# POWER_IO.net
KiCad netlist of a schematic drawn in Altium Designer
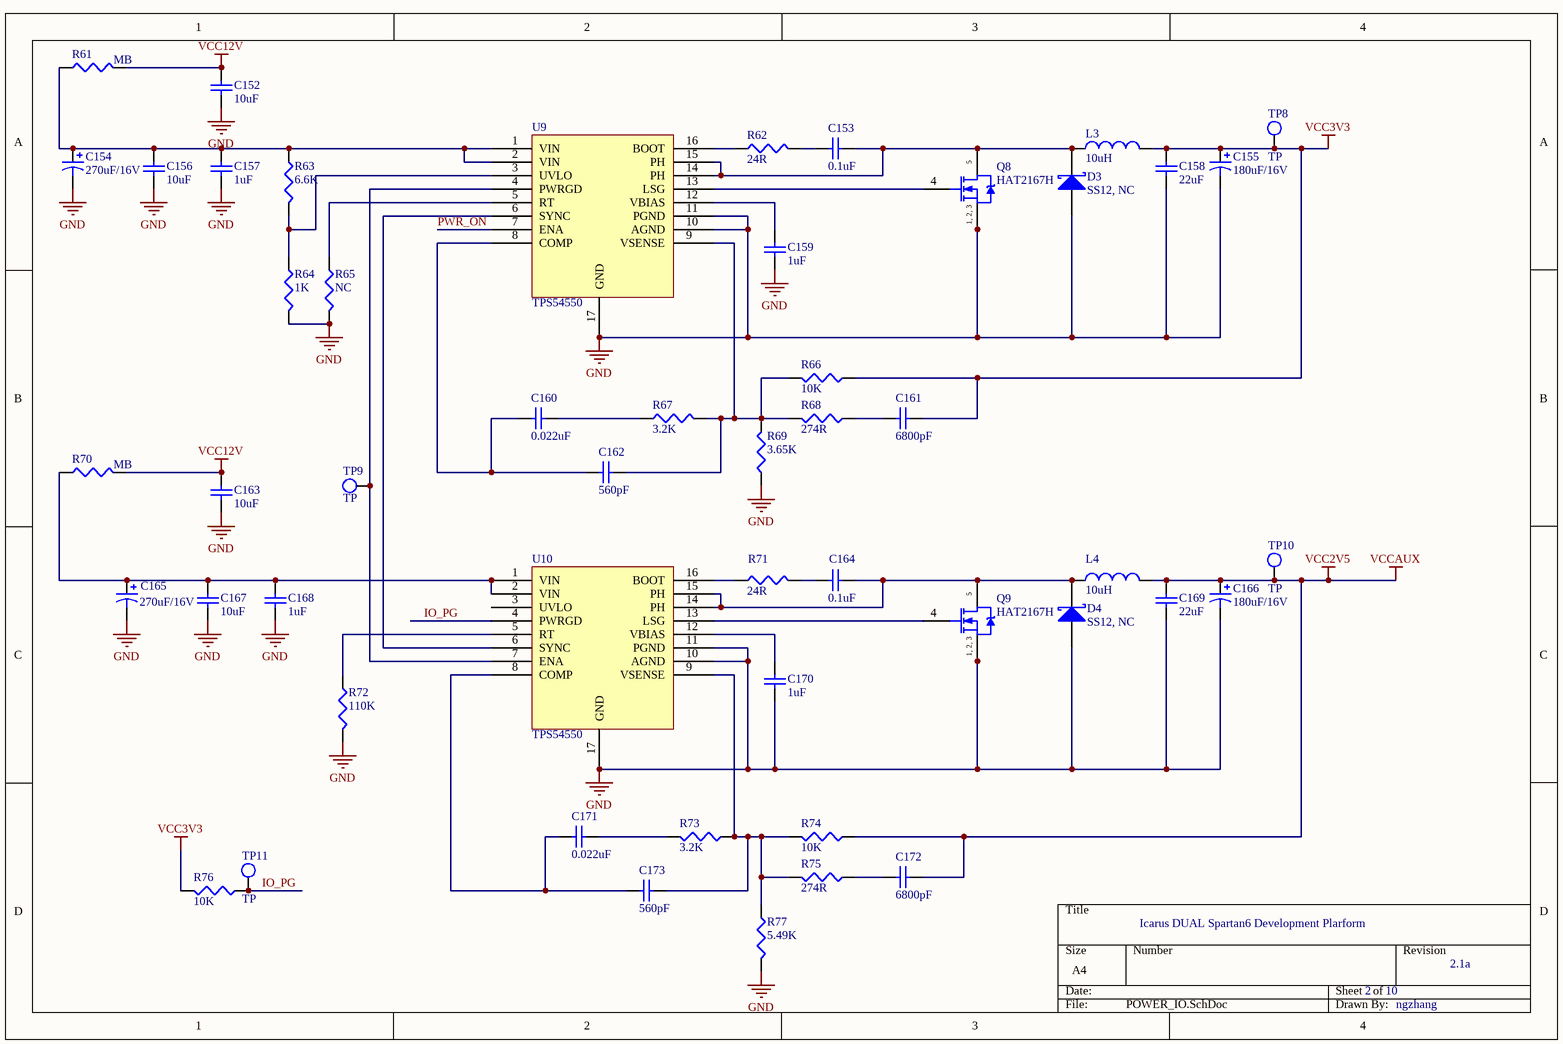
[diagram p0: POWER_IO.SchDoc]

(export (version "E")
  (design (tool "Eeschema 10.0.6"))
  (components
    (comp (ref "C152")
      (value "10uF")
      (footprint "C1206")
      (description "Capacitor (Semiconductor SIM Model)")
      (fields (field (name "PUBLISHER") "Altium Limited"))
      (libsource (lib "Miscellaneous Devices") (part "Cap Semi"))
    )
    (comp (ref "C153")
      (value "0.1uF")
      (footprint "1608[0603]")
      (description "Capacitor (Semiconductor SIM Model)")
      (fields (field (name "PUBLISHER") "Altium Limited"))
      (libsource (lib "Miscellaneous Devices") (part "Cap Semi"))
    )
    (comp (ref "C154")
      (value "270uF/16V")
      (footprint "CAP8X8")
      (description "Polarized Capacitor (Surface Mount)")
      (fields (field (name "PUBLISHER") "Altium Limited"))
      (libsource (lib "Miscellaneous Devices") (part "Cap Pol3"))
    )
    (comp (ref "C155")
      (value "180uF/16V")
      (footprint "CAP8X8")
      (description "Polarized Capacitor (Surface Mount)")
      (fields (field (name "PUBLISHER") "Altium Limited"))
      (libsource (lib "Miscellaneous Devices") (part "Cap Pol3"))
    )
    (comp (ref "C156")
      (value "10uF")
      (footprint "C1206")
      (description "Capacitor (Semiconductor SIM Model)")
      (fields (field (name "PUBLISHER") "Altium Limited"))
      (libsource (lib "Miscellaneous Devices") (part "Cap Semi"))
    )
    (comp (ref "C157")
      (value "1uF")
      (footprint "1608[0603]")
      (description "Capacitor (Semiconductor SIM Model)")
      (fields (field (name "PUBLISHER") "Altium Limited"))
      (libsource (lib "Miscellaneous Devices") (part "Cap Semi"))
    )
    (comp (ref "C158")
      (value "22uF")
      (footprint "C1206")
      (description "Capacitor (Semiconductor SIM Model)")
      (fields (field (name "PUBLISHER") "Altium Limited"))
      (libsource (lib "Miscellaneous Devices") (part "Cap Semi"))
    )
    (comp (ref "C159")
      (value "1uF")
      (footprint "1608[0603]")
      (description "Capacitor (Semiconductor SIM Model)")
      (fields (field (name "PUBLISHER") "Altium Limited"))
      (libsource (lib "Miscellaneous Devices") (part "Cap Semi"))
    )
    (comp (ref "C160")
      (value "0.022uF")
      (footprint "1608[0603]")
      (description "Capacitor (Semiconductor SIM Model)")
      (fields (field (name "PUBLISHER") "Altium Limited"))
      (libsource (lib "Miscellaneous Devices") (part "Cap Semi"))
    )
    (comp (ref "C161")
      (value "6800pF")
      (footprint "1608[0603]")
      (description "Capacitor (Semiconductor SIM Model)")
      (fields (field (name "PUBLISHER") "Altium Limited"))
      (libsource (lib "Miscellaneous Devices") (part "Cap Semi"))
    )
    (comp (ref "C162")
      (value "560pF")
      (footprint "1608[0603]")
      (description "Capacitor (Semiconductor SIM Model)")
      (fields (field (name "PUBLISHER") "Altium Limited"))
      (libsource (lib "Miscellaneous Devices") (part "Cap Semi"))
    )
    (comp (ref "C163")
      (value "10uF")
      (footprint "C1206")
      (description "Capacitor (Semiconductor SIM Model)")
      (fields (field (name "PUBLISHER") "Altium Limited"))
      (libsource (lib "Miscellaneous Devices") (part "Cap Semi"))
    )
    (comp (ref "C164")
      (value "0.1uF")
      (footprint "1608[0603]")
      (description "Capacitor (Semiconductor SIM Model)")
      (fields (field (name "PUBLISHER") "Altium Limited"))
      (libsource (lib "Miscellaneous Devices") (part "Cap Semi"))
    )
    (comp (ref "C165")
      (value "270uF/16V")
      (footprint "CAP8X8")
      (description "Polarized Capacitor (Surface Mount)")
      (fields (field (name "PUBLISHER") "Altium Limited"))
      (libsource (lib "Miscellaneous Devices") (part "Cap Pol3"))
    )
    (comp (ref "C166")
      (value "180uF/16V")
      (footprint "CAP8X8")
      (description "Polarized Capacitor (Surface Mount)")
      (fields (field (name "PUBLISHER") "Altium Limited"))
      (libsource (lib "Miscellaneous Devices") (part "Cap Pol3"))
    )
    (comp (ref "C167")
      (value "10uF")
      (footprint "C1206")
      (description "Capacitor (Semiconductor SIM Model)")
      (fields (field (name "PUBLISHER") "Altium Limited"))
      (libsource (lib "Miscellaneous Devices") (part "Cap Semi"))
    )
    (comp (ref "C168")
      (value "1uF")
      (footprint "1608[0603]")
      (description "Capacitor (Semiconductor SIM Model)")
      (fields (field (name "PUBLISHER") "Altium Limited"))
      (libsource (lib "Miscellaneous Devices") (part "Cap Semi"))
    )
    (comp (ref "C169")
      (value "22uF")
      (footprint "C1206")
      (description "Capacitor (Semiconductor SIM Model)")
      (fields (field (name "PUBLISHER") "Altium Limited"))
      (libsource (lib "Miscellaneous Devices") (part "Cap Semi"))
    )
    (comp (ref "C170")
      (value "1uF")
      (footprint "1608[0603]")
      (description "Capacitor (Semiconductor SIM Model)")
      (fields (field (name "PUBLISHER") "Altium Limited"))
      (libsource (lib "Miscellaneous Devices") (part "Cap Semi"))
    )
    (comp (ref "C171")
      (value "0.022uF")
      (footprint "1608[0603]")
      (description "Capacitor (Semiconductor SIM Model)")
      (fields (field (name "PUBLISHER") "Altium Limited"))
      (libsource (lib "Miscellaneous Devices") (part "Cap Semi"))
    )
    (comp (ref "C172")
      (value "6800pF")
      (footprint "1608[0603]")
      (description "Capacitor (Semiconductor SIM Model)")
      (fields (field (name "PUBLISHER") "Altium Limited"))
      (libsource (lib "Miscellaneous Devices") (part "Cap Semi"))
    )
    (comp (ref "C173")
      (value "560pF")
      (footprint "1608[0603]")
      (description "Capacitor (Semiconductor SIM Model)")
      (fields (field (name "PUBLISHER") "Altium Limited"))
      (libsource (lib "Miscellaneous Devices") (part "Cap Semi"))
    )
    (comp (ref "D3")
      (value "SS12, NC")
      (footprint "SMA")
      (description "Schottky Rectifier")
      (fields (field (name "PUBLISHER") "Altium Limited"))
      (libsource (lib "IR Rectifier - Schottky") (part "10MQ060N"))
    )
    (comp (ref "D4")
      (value "SS12, NC")
      (footprint "SMA")
      (description "Schottky Rectifier")
      (fields (field (name "PUBLISHER") "Altium Limited"))
      (libsource (lib "IR Rectifier - Schottky") (part "10MQ060N"))
    )
    (comp (ref "L3")
      (value "10uH")
      (footprint "IHLP4040")
      (description "Inductor")
      (fields (field (name "Comment") "IHLP4040DZ11") (field (name "PUBLISHER") "Altium Limited"))
      (libsource (lib "Miscellaneous Devices") (part "Inductor"))
    )
    (comp (ref "L4")
      (value "10uH")
      (footprint "IHLP4040")
      (description "Inductor")
      (fields (field (name "Comment") "IHLP4040DZ11") (field (name "PUBLISHER") "Altium Limited"))
      (libsource (lib "Miscellaneous Devices") (part "Inductor"))
    )
    (comp (ref "Q8") (value "HAT2167H") (footprint "LFPAK") (libsource (lib "S6") (part "HAT216X")))
    (comp (ref "Q9") (value "HAT2167H") (footprint "LFPAK") (libsource (lib "S6") (part "HAT216X")))
    (comp (ref "R61")
      (value "MB")
      (footprint "C1206")
      (description "Resistor")
      (fields (field (name "PUBLISHER") "Altium Limited"))
      (libsource (lib "Miscellaneous Devices") (part "Res3"))
    )
    (comp (ref "R62")
      (value "24R")
      (footprint "J1-0603")
      (description "Resistor")
      (fields (field (name "PUBLISHER") "Altium Limited"))
      (libsource (lib "Miscellaneous Devices") (part "Res3"))
    )
    (comp (ref "R63")
      (value "6.6K")
      (footprint "J1-0603")
      (description "Resistor")
      (fields (field (name "PUBLISHER") "Altium Limited"))
      (libsource (lib "Miscellaneous Devices") (part "Res3"))
    )
    (comp (ref "R64")
      (value "1K")
      (footprint "J1-0603")
      (description "Resistor")
      (fields (field (name "PUBLISHER") "Altium Limited"))
      (libsource (lib "Miscellaneous Devices") (part "Res3"))
    )
    (comp (ref "R65")
      (value "NC")
      (footprint "J1-0603")
      (description "Resistor")
      (fields (field (name "PUBLISHER") "Altium Limited"))
      (libsource (lib "Miscellaneous Devices") (part "Res3"))
    )
    (comp (ref "R66")
      (value "10K")
      (footprint "J1-0603")
      (description "Resistor")
      (fields (field (name "PUBLISHER") "Altium Limited"))
      (libsource (lib "Miscellaneous Devices") (part "Res3"))
    )
    (comp (ref "R67")
      (value "3.2K")
      (footprint "J1-0603")
      (description "Resistor")
      (fields (field (name "PUBLISHER") "Altium Limited"))
      (libsource (lib "Miscellaneous Devices") (part "Res3"))
    )
    (comp (ref "R68")
      (value "274R")
      (footprint "J1-0603")
      (description "Resistor")
      (fields (field (name "PUBLISHER") "Altium Limited"))
      (libsource (lib "Miscellaneous Devices") (part "Res3"))
    )
    (comp (ref "R69")
      (value "3.65K")
      (footprint "J1-0603")
      (description "Resistor")
      (fields (field (name "PUBLISHER") "Altium Limited"))
      (libsource (lib "Miscellaneous Devices") (part "Res3"))
    )
    (comp (ref "R70")
      (value "MB")
      (footprint "C1206")
      (description "Resistor")
      (fields (field (name "PUBLISHER") "Altium Limited"))
      (libsource (lib "Miscellaneous Devices") (part "Res3"))
    )
    (comp (ref "R71")
      (value "24R")
      (footprint "J1-0603")
      (description "Resistor")
      (fields (field (name "PUBLISHER") "Altium Limited"))
      (libsource (lib "Miscellaneous Devices") (part "Res3"))
    )
    (comp (ref "R72")
      (value "110K")
      (footprint "J1-0603")
      (description "Resistor")
      (fields (field (name "PUBLISHER") "Altium Limited"))
      (libsource (lib "Miscellaneous Devices") (part "Res3"))
    )
    (comp (ref "R73")
      (value "3.2K")
      (footprint "J1-0603")
      (description "Resistor")
      (fields (field (name "PUBLISHER") "Altium Limited"))
      (libsource (lib "Miscellaneous Devices") (part "Res3"))
    )
    (comp (ref "R74")
      (value "10K")
      (footprint "J1-0603")
      (description "Resistor")
      (fields (field (name "PUBLISHER") "Altium Limited"))
      (libsource (lib "Miscellaneous Devices") (part "Res3"))
    )
    (comp (ref "R75")
      (value "274R")
      (footprint "J1-0603")
      (description "Resistor")
      (fields (field (name "PUBLISHER") "Altium Limited"))
      (libsource (lib "Miscellaneous Devices") (part "Res3"))
    )
    (comp (ref "R76")
      (value "10K")
      (footprint "J1-0603")
      (description "Resistor")
      (fields (field (name "PUBLISHER") "Altium Limited"))
      (libsource (lib "Miscellaneous Devices") (part "Res3"))
    )
    (comp (ref "R77")
      (value "5.49K")
      (footprint "J1-0603")
      (description "Resistor")
      (fields (field (name "PUBLISHER") "Altium Limited"))
      (libsource (lib "Miscellaneous Devices") (part "Res3"))
    )
    (comp (ref "TP8") (value "TP") (footprint "TP") (libsource (lib "S6") (part "TP")))
    (comp (ref "TP9") (value "TP") (footprint "TP") (libsource (lib "S6") (part "TP")))
    (comp (ref "TP10") (value "TP") (footprint "TP") (libsource (lib "S6") (part "TP")))
    (comp (ref "TP11") (value "TP") (footprint "TP") (libsource (lib "S6") (part "TP")))
    (comp (ref "U9") (value "TPS54550") (footprint "TSSOP16_PP") (libsource (lib "S6") (part "TPS54350")))
    (comp (ref "U10") (value "TPS54550") (footprint "TSSOP16_PP") (libsource (lib "S6") (part "TPS54350")))
  )
  (nets
    (net (code "1") (name "/IO_PG") (class "Default")
      (node (ref "R76") (pin "1") (pinfunction "1_1") (pintype "passive"))
      (node (ref "TP11") (pin "1") (pinfunction "TP_1") (pintype "passive"))
      (node (ref "U10") (pin "4") (pinfunction "PWRGD_4") (pintype "passive"))
    )
    (net (code "2") (name "/PWR_ON") (class "Default")
      (node (ref "U9") (pin "7") (pinfunction "ENA_7") (pintype "passive"))
    )
    (net (code "3") (name "GND") (class "Default")
      (node (ref "C152") (pin "1") (pinfunction "1_1") (pintype "passive"))
      (node (ref "C154") (pin "2") (pinfunction "2_2") (pintype "passive"))
      (node (ref "C155") (pin "2") (pinfunction "2_2") (pintype "passive"))
      (node (ref "C156") (pin "1") (pinfunction "1_1") (pintype "passive"))
      (node (ref "C157") (pin "1") (pinfunction "1_1") (pintype "passive"))
      (node (ref "C158") (pin "1") (pinfunction "1_1") (pintype "passive"))
      (node (ref "C159") (pin "1") (pinfunction "1_1") (pintype "passive"))
      (node (ref "C163") (pin "1") (pinfunction "1_1") (pintype "passive"))
      (node (ref "C165") (pin "2") (pinfunction "2_2") (pintype "passive"))
      (node (ref "C166") (pin "2") (pinfunction "2_2") (pintype "passive"))
      (node (ref "C167") (pin "1") (pinfunction "1_1") (pintype "passive"))
      (node (ref "C168") (pin "1") (pinfunction "1_1") (pintype "passive"))
      (node (ref "C169") (pin "1") (pinfunction "1_1") (pintype "passive"))
      (node (ref "C170") (pin "2") (pinfunction "2_2") (pintype "passive"))
      (node (ref "D3") (pin "1") (pinfunction "A_1") (pintype "passive"))
      (node (ref "D4") (pin "1") (pinfunction "A_1") (pintype "passive"))
      (node (ref "Q8") (pin "1") (pinfunction "S_1") (pintype "passive"))
      (node (ref "Q8") (pin "2") (pinfunction "S_2") (pintype "passive"))
      (node (ref "Q8") (pin "3") (pinfunction "S_3") (pintype "passive"))
      (node (ref "Q9") (pin "1") (pinfunction "S_1") (pintype "passive"))
      (node (ref "Q9") (pin "2") (pinfunction "S_2") (pintype "passive"))
      (node (ref "Q9") (pin "3") (pinfunction "S_3") (pintype "passive"))
      (node (ref "R64") (pin "2") (pinfunction "2_2") (pintype "passive"))
      (node (ref "R65") (pin "2") (pinfunction "2_2") (pintype "passive"))
      (node (ref "R69") (pin "1") (pinfunction "1_1") (pintype "passive"))
      (node (ref "R72") (pin "2") (pinfunction "2_2") (pintype "passive"))
      (node (ref "R77") (pin "2") (pinfunction "2_2") (pintype "passive"))
      (node (ref "U10") (pin "10") (pinfunction "AGND_10") (pintype "passive"))
      (node (ref "U10") (pin "11") (pinfunction "PGND_11") (pintype "passive"))
      (node (ref "U10") (pin "17") (pinfunction "GND_17") (pintype "power_in"))
      (node (ref "U9") (pin "10") (pinfunction "AGND_10") (pintype "passive"))
      (node (ref "U9") (pin "11") (pinfunction "PGND_11") (pintype "passive"))
      (node (ref "U9") (pin "17") (pinfunction "GND_17") (pintype "power_in"))
    )
    (net (code "4") (name "Net-(C153-Pad1)") (class "Default")
      (node (ref "C153") (pin "1") (pinfunction "1_1") (pintype "passive"))
      (node (ref "R62") (pin "2") (pinfunction "2_2") (pintype "passive"))
    )
    (net (code "5") (name "Net-(C154-Pad1)") (class "Default")
      (node (ref "C154") (pin "1") (pinfunction "1_1") (pintype "passive"))
      (node (ref "C156") (pin "2") (pinfunction "2_2") (pintype "passive"))
      (node (ref "C157") (pin "2") (pinfunction "2_2") (pintype "passive"))
      (node (ref "R61") (pin "1") (pinfunction "1_1") (pintype "passive"))
      (node (ref "R63") (pin "1") (pinfunction "1_1") (pintype "passive"))
      (node (ref "U9") (pin "1") (pinfunction "VIN_1") (pintype "power_in"))
      (node (ref "U9") (pin "2") (pinfunction "VIN_2") (pintype "power_in"))
    )
    (net (code "6") (name "Net-(C160-Pad2)") (class "Default")
      (node (ref "C160") (pin "2") (pinfunction "2_2") (pintype "passive"))
      (node (ref "R67") (pin "1") (pinfunction "1_1") (pintype "passive"))
    )
    (net (code "7") (name "Net-(C161-Pad1)") (class "Default")
      (node (ref "C161") (pin "1") (pinfunction "1_1") (pintype "passive"))
      (node (ref "R68") (pin "1") (pinfunction "1_1") (pintype "passive"))
    )
    (net (code "8") (name "Net-(C164-Pad2)") (class "Default")
      (node (ref "C164") (pin "2") (pinfunction "2_2") (pintype "passive"))
      (node (ref "R71") (pin "2") (pinfunction "2_2") (pintype "passive"))
    )
    (net (code "9") (name "Net-(C165-Pad1)") (class "Default")
      (node (ref "C165") (pin "1") (pinfunction "1_1") (pintype "passive"))
      (node (ref "C167") (pin "2") (pinfunction "2_2") (pintype "passive"))
      (node (ref "C168") (pin "2") (pinfunction "2_2") (pintype "passive"))
      (node (ref "R70") (pin "1") (pinfunction "1_1") (pintype "passive"))
      (node (ref "U10") (pin "1") (pinfunction "VIN_1") (pintype "power_in"))
      (node (ref "U10") (pin "2") (pinfunction "VIN_2") (pintype "power_in"))
    )
    (net (code "10") (name "Net-(C171-Pad2)") (class "Default")
      (node (ref "C171") (pin "2") (pinfunction "2_2") (pintype "passive"))
      (node (ref "R73") (pin "2") (pinfunction "2_2") (pintype "passive"))
    )
    (net (code "11") (name "Net-(C172-Pad1)") (class "Default")
      (node (ref "C172") (pin "1") (pinfunction "1_1") (pintype "passive"))
      (node (ref "R75") (pin "1") (pinfunction "1_1") (pintype "passive"))
    )
    (net (code "12") (name "Net-(D3-K)") (class "Default")
      (node (ref "C153") (pin "2") (pinfunction "2_2") (pintype "passive"))
      (node (ref "D3") (pin "2") (pinfunction "K_2") (pintype "passive"))
      (node (ref "L3") (pin "1") (pinfunction "1_1") (pintype "passive"))
      (node (ref "Q8") (pin "5") (pinfunction "D_5") (pintype "passive"))
      (node (ref "U9") (pin "14") (pinfunction "PH_14") (pintype "passive"))
      (node (ref "U9") (pin "15") (pinfunction "PH_15") (pintype "passive"))
    )
    (net (code "13") (name "Net-(D4-K)") (class "Default")
      (node (ref "C164") (pin "1") (pinfunction "1_1") (pintype "passive"))
      (node (ref "D4") (pin "2") (pinfunction "K_2") (pintype "passive"))
      (node (ref "L4") (pin "1") (pinfunction "1_1") (pintype "passive"))
      (node (ref "Q9") (pin "5") (pinfunction "D_5") (pintype "passive"))
      (node (ref "U10") (pin "14") (pinfunction "PH_14") (pintype "passive"))
      (node (ref "U10") (pin "15") (pinfunction "PH_15") (pintype "passive"))
    )
    (net (code "14") (name "Net-(Q8-G)") (class "Default")
      (node (ref "Q8") (pin "4") (pinfunction "G_4") (pintype "passive"))
      (node (ref "U9") (pin "13") (pinfunction "LSG_13") (pintype "passive"))
    )
    (net (code "15") (name "Net-(Q9-G)") (class "Default")
      (node (ref "Q9") (pin "4") (pinfunction "G_4") (pintype "passive"))
      (node (ref "U10") (pin "13") (pinfunction "LSG_13") (pintype "passive"))
    )
    (net (code "16") (name "Net-(TP9-TP)") (class "Default")
      (node (ref "TP9") (pin "1") (pinfunction "TP_1") (pintype "passive"))
      (node (ref "U10") (pin "7") (pinfunction "ENA_7") (pintype "passive"))
      (node (ref "U9") (pin "4") (pinfunction "PWRGD_4") (pintype "passive"))
    )
    (net (code "17") (name "Net-(U9-BOOT)") (class "Default")
      (node (ref "R62") (pin "1") (pinfunction "1_1") (pintype "passive"))
      (node (ref "U9") (pin "16") (pinfunction "BOOT_16") (pintype "passive"))
    )
    (net (code "18") (name "Net-(U9-COMP)") (class "Default")
      (node (ref "C160") (pin "1") (pinfunction "1_1") (pintype "passive"))
      (node (ref "C162") (pin "1") (pinfunction "1_1") (pintype "passive"))
      (node (ref "U9") (pin "8") (pinfunction "COMP_8") (pintype "passive"))
    )
    (net (code "19") (name "Net-(U9-RT)") (class "Default")
      (node (ref "R65") (pin "1") (pinfunction "1_1") (pintype "passive"))
      (node (ref "U9") (pin "5") (pinfunction "RT_5") (pintype "passive"))
    )
    (net (code "20") (name "Net-(U9-UVLO)") (class "Default")
      (node (ref "R63") (pin "2") (pinfunction "2_2") (pintype "passive"))
      (node (ref "R64") (pin "1") (pinfunction "1_1") (pintype "passive"))
      (node (ref "U9") (pin "3") (pinfunction "UVLO_3") (pintype "passive"))
    )
    (net (code "21") (name "Net-(U9-VBIAS)") (class "Default")
      (node (ref "C159") (pin "2") (pinfunction "2_2") (pintype "passive"))
      (node (ref "U9") (pin "12") (pinfunction "VBIAS_12") (pintype "passive"))
    )
    (net (code "22") (name "Net-(U9-VSENSE)") (class "Default")
      (node (ref "C162") (pin "2") (pinfunction "2_2") (pintype "passive"))
      (node (ref "R66") (pin "2") (pinfunction "2_2") (pintype "passive"))
      (node (ref "R67") (pin "2") (pinfunction "2_2") (pintype "passive"))
      (node (ref "R68") (pin "2") (pinfunction "2_2") (pintype "passive"))
      (node (ref "R69") (pin "2") (pinfunction "2_2") (pintype "passive"))
      (node (ref "U9") (pin "9") (pinfunction "VSENSE_9") (pintype "passive"))
    )
    (net (code "23") (name "Net-(U10-BOOT)") (class "Default")
      (node (ref "R71") (pin "1") (pinfunction "1_1") (pintype "passive"))
      (node (ref "U10") (pin "16") (pinfunction "BOOT_16") (pintype "passive"))
    )
    (net (code "24") (name "Net-(U10-COMP)") (class "Default")
      (node (ref "C171") (pin "1") (pinfunction "1_1") (pintype "passive"))
      (node (ref "C173") (pin "1") (pinfunction "1_1") (pintype "passive"))
      (node (ref "U10") (pin "8") (pinfunction "COMP_8") (pintype "passive"))
    )
    (net (code "25") (name "Net-(U10-RT)") (class "Default")
      (node (ref "R72") (pin "1") (pinfunction "1_1") (pintype "passive"))
      (node (ref "U10") (pin "5") (pinfunction "RT_5") (pintype "passive"))
    )
    (net (code "26") (name "Net-(U10-SYNC)") (class "Default")
      (node (ref "U10") (pin "6") (pinfunction "SYNC_6") (pintype "passive"))
      (node (ref "U9") (pin "6") (pinfunction "SYNC_6") (pintype "passive"))
    )
    (net (code "27") (name "Net-(U10-VBIAS)") (class "Default")
      (node (ref "C170") (pin "1") (pinfunction "1_1") (pintype "passive"))
      (node (ref "U10") (pin "12") (pinfunction "VBIAS_12") (pintype "passive"))
    )
    (net (code "28") (name "Net-(U10-VSENSE)") (class "Default")
      (node (ref "C173") (pin "2") (pinfunction "2_2") (pintype "passive"))
      (node (ref "R73") (pin "1") (pinfunction "1_1") (pintype "passive"))
      (node (ref "R74") (pin "2") (pinfunction "2_2") (pintype "passive"))
      (node (ref "R75") (pin "2") (pinfunction "2_2") (pintype "passive"))
      (node (ref "R77") (pin "1") (pinfunction "1_1") (pintype "passive"))
      (node (ref "U10") (pin "9") (pinfunction "VSENSE_9") (pintype "passive"))
    )
    (net (code "29") (name "VCC2V5") (class "Default")
      (node (ref "C166") (pin "1") (pinfunction "1_1") (pintype "passive"))
      (node (ref "C169") (pin "2") (pinfunction "2_2") (pintype "passive"))
      (node (ref "C172") (pin "2") (pinfunction "2_2") (pintype "passive"))
      (node (ref "L4") (pin "2") (pinfunction "2_2") (pintype "passive"))
      (node (ref "R74") (pin "1") (pinfunction "1_1") (pintype "passive"))
      (node (ref "TP10") (pin "1") (pinfunction "TP_1") (pintype "passive"))
    )
    (net (code "30") (name "VCC3V3") (class "Default")
      (node (ref "C155") (pin "1") (pinfunction "1_1") (pintype "passive"))
      (node (ref "C158") (pin "2") (pinfunction "2_2") (pintype "passive"))
      (node (ref "C161") (pin "2") (pinfunction "2_2") (pintype "passive"))
      (node (ref "L3") (pin "2") (pinfunction "2_2") (pintype "passive"))
      (node (ref "R66") (pin "1") (pinfunction "1_1") (pintype "passive"))
      (node (ref "R76") (pin "2") (pinfunction "2_2") (pintype "passive"))
      (node (ref "TP8") (pin "1") (pinfunction "TP_1") (pintype "passive"))
    )
    (net (code "31") (name "VCC12V") (class "Default")
      (node (ref "C152") (pin "2") (pinfunction "2_2") (pintype "passive"))
      (node (ref "C163") (pin "2") (pinfunction "2_2") (pintype "passive"))
      (node (ref "R61") (pin "2") (pinfunction "2_2") (pintype "passive"))
      (node (ref "R70") (pin "2") (pinfunction "2_2") (pintype "passive"))
    )
    (net (code "32") (name "unconnected-(U10-UVLO-Pad3)") (class "Default")
      (node (ref "U10") (pin "3") (pinfunction "UVLO_3") (pintype "passive"))
    )
  )
)
